# 1_MCU.net
KiCad netlist of a schematic drawn in Altium Designer
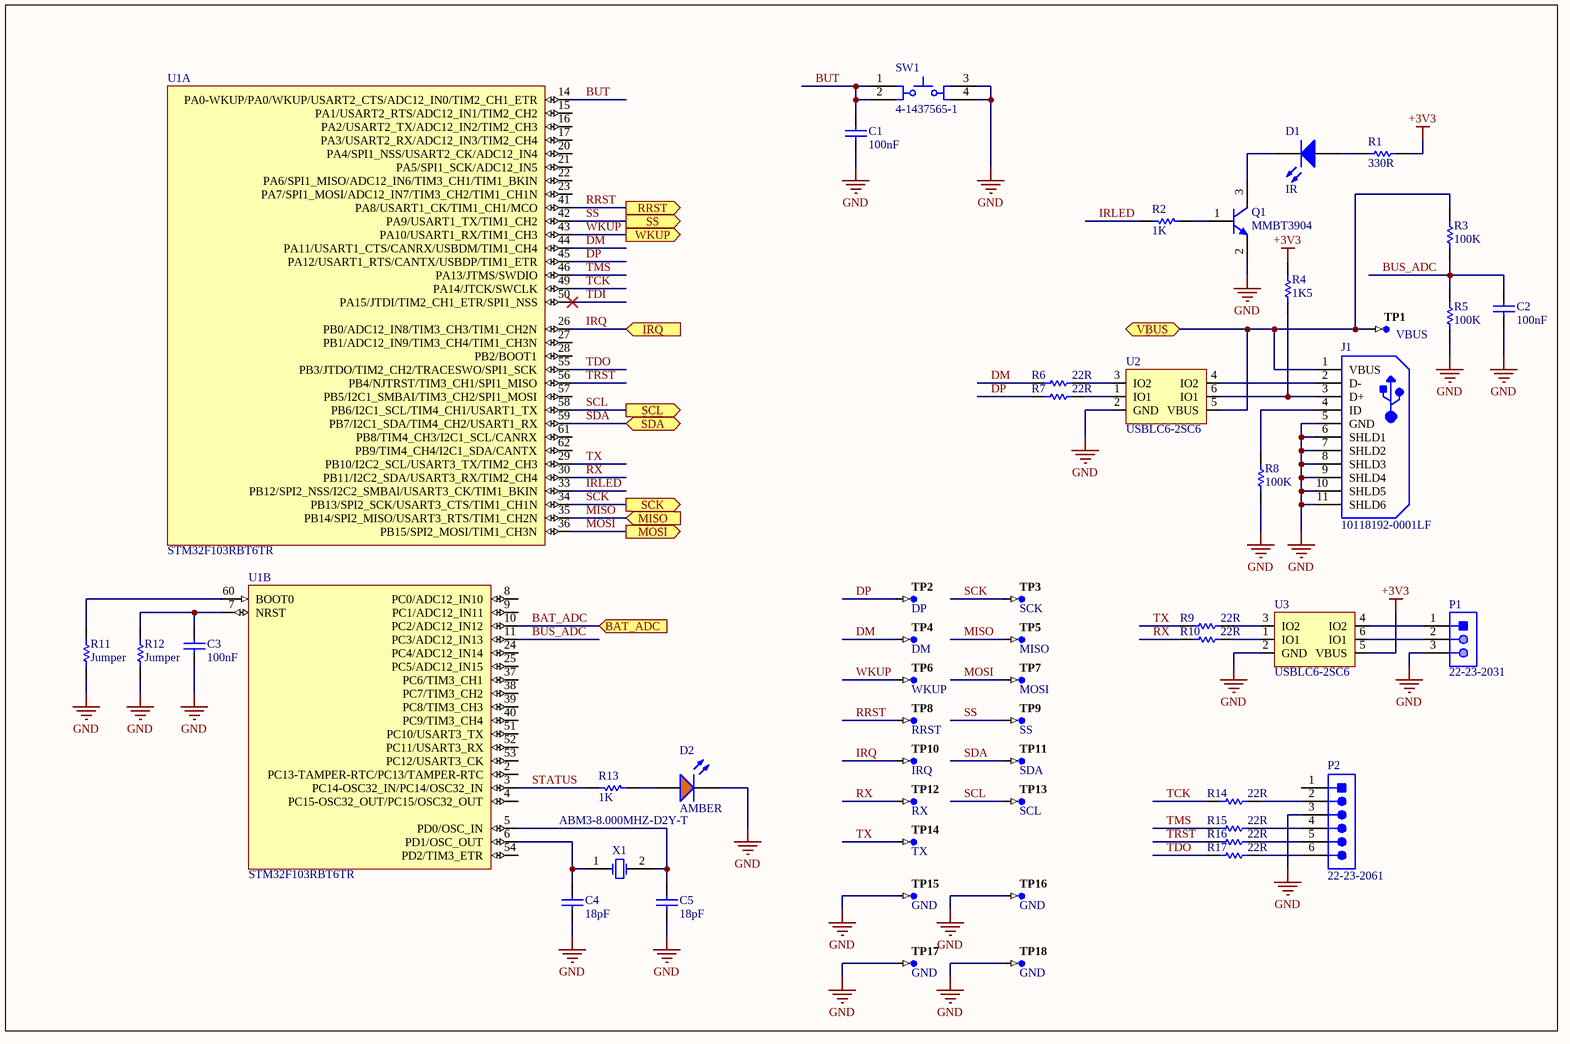
[diagram p0: 1_MCU.SchDoc]

(export (version "E")
  (design (tool "Eeschema 10.0.6"))
  (components
    (comp (ref "C1")
      (value "100nF")
      (footprint "CAPC0603(1608)100_M")
      (description "CAP 100nF 25V ±20% 0603 (1608 Metric) Thickness 1mm SMD")
      (fields (field (name "TOLERANCE") "Â±20%"))
      (libsource (lib "Altium Content Vault") (part "CAP"))
    )
    (comp (ref "C2")
      (value "100nF")
      (footprint "CAPC0603(1608)100_M")
      (description "CAP 100nF 25V ±20% 0603 (1608 Metric) Thickness 1mm SMD")
      (fields (field (name "TOLERANCE") "Â±20%"))
      (libsource (lib "Altium Content Vault") (part "CAP"))
    )
    (comp (ref "C3")
      (value "100nF")
      (footprint "CAPC0603(1608)100_M")
      (description "CAP 100nF 25V ±20% 0603 (1608 Metric) Thickness 1mm SMD")
      (fields (field (name "TOLERANCE") "Â±20%"))
      (libsource (lib "Altium Content Vault") (part "CAP"))
    )
    (comp (ref "C4")
      (value "18pF")
      (footprint "CAPC0603(1608)100_M")
      (description "CAP 18pF 25V ±0.5pF 0603 (1608 Metric) Thickness 1mm SMD")
      (fields (field (name "TOLERANCE") "Â±0.5pF"))
      (libsource (lib "Altium Content Vault") (part "CAP"))
    )
    (comp (ref "C5")
      (value "18pF")
      (footprint "CAPC0603(1608)100_M")
      (description "CAP 18pF 25V ±0.5pF 0603 (1608 Metric) Thickness 1mm SMD")
      (fields (field (name "TOLERANCE") "Â±0.5pF"))
      (libsource (lib "Altium Content Vault") (part "CAP"))
    )
    (comp (ref "D1")
      (value "IR")
      (footprint "Type 3mm")
      (description "THT LED round mono-color color lens, WL-TMRW, Super Red")
      (fields (field (name "PARTNUMBER") "151031SS04000") (field (name "MANUFACTURER") "Wuerth Elektronik"))
      (libsource (lib "Altium Content Vault") (part "WE-LED_K1A2-2"))
    )
    (comp (ref "D2")
      (value "AMBER")
      (footprint "LTST-C171AKT_V")
      (description "LED AMBER CLR THIN 0805 SMD")
      (fields (field (name "PARTNUMBER") "LTST-C171AKT") (field (name "MANUFACTURER") "Lite-On"))
      (libsource (lib "Altium Content Vault") (part "LED_AMBER_AC"))
    )
    (comp (ref "J1")
      (value "10118192-0001LF")
      (footprint "FCI-10118192-0001LF-5_V")
      (description "Micro USB B Type Receptacle, -55 to 85 degC, 5-Pin SMD, RoHS, Tape and Reel")
      (fields (field (name "MANUFACTURER") "FCI"))
      (libsource (lib "Altium Content Vault") (part "USB-5-6SHLD"))
    )
    (comp (ref "P1")
      (value "22-23-2031")
      (footprint "MOLX-22-23-2031_V")
      (description "Male Header, Pitch 2.54 mm, 1 x 3 Position, Height 8.18 mm, Tail Length 3.56 mm, RoHS, Bulk")
      (fields (field (name "MANUFACTURER") "Molex"))
      (libsource (lib "Altium Content Vault") (part "CN-1P-M-R3"))
    )
    (comp (ref "P2")
      (value "22-23-2061")
      (footprint "MOLX-22-23-2061_V")
      (fields (field (name "MANUFACTURER") "Molex"))
      (libsource (lib "Altium Content Vault") (part "CN-1P-M-R6"))
    )
    (comp (ref "Q1")
      (value "MMBT3904")
      (footprint "FAIR-SOT23-3_V")
      (description "NPN General Purpose Amplifier, 40 V, 0.2 A, -55 to 150 degC, 3-Pin SOT23, RoHS, Tape and Reel")
      (fields (field (name "TOLERANCE") "30ppm"))
      (libsource (lib "Altium Content Vault") (part "BJT-NPN-BEC-3"))
    )
    (comp (ref "R1")
      (value "330R")
      (footprint "RESC0603(1608)_M")
      (description "330R 0.1W 1% 0603 (1608 Metric)  SMD")
      (fields (field (name "TOLERANCE") "1 %") (field (name "POWER") "0.1 W"))
      (libsource (lib "Altium Content Vault") (part "RES"))
    )
    (comp (ref "R2")
      (value "1K")
      (footprint "RESC0603(1608)_M")
      (description "1K 0.1W 1% 0603 (1608 Metric)  SMD")
      (fields (field (name "TOLERANCE") "1 %") (field (name "POWER") "0.1 W"))
      (libsource (lib "Altium Content Vault") (part "RES"))
    )
    (comp (ref "R3")
      (value "100K")
      (footprint "RESC0603(1608)_M")
      (description "100K 0.1W 1% 0603 (1608 Metric)  SMD")
      (fields (field (name "POWER") "0.1 W") (field (name "TOLERANCE") "1 %"))
      (libsource (lib "Altium Content Vault") (part "RES"))
    )
    (comp (ref "R4")
      (value "1K5")
      (footprint "RESC0603(1608)_M")
      (description "1K5 0.1W 1% 0603 (1608 Metric)  SMD")
      (fields (field (name "POWER") "0.1 W") (field (name "TOLERANCE") "1 %"))
      (libsource (lib "Altium Content Vault") (part "RES"))
    )
    (comp (ref "R5")
      (value "100K")
      (footprint "RESC0603(1608)_M")
      (description "100K 0.1W 1% 0603 (1608 Metric)  SMD")
      (fields (field (name "POWER") "0.1 W") (field (name "TOLERANCE") "1 %"))
      (libsource (lib "Altium Content Vault") (part "RES"))
    )
    (comp (ref "R6")
      (value "22R")
      (footprint "RESC0603(1608)_M")
      (description "22R 0.1W 1% 0603 (1608 Metric)  SMD")
      (fields (field (name "POWER") "0.1 W") (field (name "TOLERANCE") "1 %"))
      (libsource (lib "Altium Content Vault") (part "RES"))
    )
    (comp (ref "R7")
      (value "22R")
      (footprint "RESC0603(1608)_M")
      (description "22R 0.1W 1% 0603 (1608 Metric)  SMD")
      (fields (field (name "POWER") "0.1 W") (field (name "TOLERANCE") "1 %"))
      (libsource (lib "Altium Content Vault") (part "RES"))
    )
    (comp (ref "R8")
      (value "100K")
      (footprint "RESC0603(1608)_M")
      (description "100K 0.1W 1% 0603 (1608 Metric)  SMD")
      (fields (field (name "POWER") "0.1 W") (field (name "TOLERANCE") "1 %"))
      (libsource (lib "Altium Content Vault") (part "RES"))
    )
    (comp (ref "R9")
      (value "22R")
      (footprint "RESC0603(1608)_M")
      (description "22R 0.1W 1% 0603 (1608 Metric)  SMD")
      (fields (field (name "POWER") "0.1 W") (field (name "TOLERANCE") "1 %"))
      (libsource (lib "Altium Content Vault") (part "RES"))
    )
    (comp (ref "R10")
      (value "22R")
      (footprint "RESC0603(1608)_M")
      (description "22R 0.1W 1% 0603 (1608 Metric)  SMD")
      (fields (field (name "POWER") "0.1 W") (field (name "TOLERANCE") "1 %"))
      (libsource (lib "Altium Content Vault") (part "RES"))
    )
    (comp (ref "R11")
      (value "Jumper")
      (footprint "RESC0805(2012)_M")
      (description "Jumper 0805 (2012 Metric)")
      (fields (field (name "TOLERANCE") "None"))
      (libsource (lib "Altium Content Vault") (part "RES"))
    )
    (comp (ref "R12")
      (value "Jumper")
      (footprint "RESC0805(2012)_M")
      (description "Jumper 0805 (2012 Metric)")
      (fields (field (name "TOLERANCE") "None"))
      (libsource (lib "Altium Content Vault") (part "RES"))
    )
    (comp (ref "R13")
      (value "1K")
      (footprint "RESC0603(1608)_M")
      (description "1K 0.1W 1% 0603 (1608 Metric)  SMD")
      (fields (field (name "TOLERANCE") "1 %") (field (name "POWER") "0.1 W"))
      (libsource (lib "Altium Content Vault") (part "RES"))
    )
    (comp (ref "R14")
      (value "22R")
      (footprint "RESC0603(1608)_M")
      (description "22R 0.1W 1% 0603 (1608 Metric)  SMD")
      (fields (field (name "POWER") "0.1 W") (field (name "TOLERANCE") "1 %"))
      (libsource (lib "Altium Content Vault") (part "RES"))
    )
    (comp (ref "R15")
      (value "22R")
      (footprint "RESC0603(1608)_M")
      (description "22R 0.1W 1% 0603 (1608 Metric)  SMD")
      (fields (field (name "POWER") "0.1 W") (field (name "TOLERANCE") "1 %"))
      (libsource (lib "Altium Content Vault") (part "RES"))
    )
    (comp (ref "R16")
      (value "22R")
      (footprint "RESC0603(1608)_M")
      (description "22R 0.1W 1% 0603 (1608 Metric)  SMD")
      (fields (field (name "POWER") "0.1 W") (field (name "TOLERANCE") "1 %"))
      (libsource (lib "Altium Content Vault") (part "RES"))
    )
    (comp (ref "R17")
      (value "22R")
      (footprint "RESC0603(1608)_M")
      (description "22R 0.1W 1% 0603 (1608 Metric)  SMD")
      (fields (field (name "POWER") "0.1 W") (field (name "TOLERANCE") "1 %"))
      (libsource (lib "Altium Content Vault") (part "RES"))
    )
    (comp (ref "SW1")
      (value "4-1437565-1")
      (footprint "TECO-4-1437565-1_V")
      (description "Tactile Switch, 50 mA, 12 VDC, -20 to 85 degC, 4-Pin SMD, RoHS, Bulk")
      (fields (field (name "MANUFACTURER") "TEConnectivity/AMPBrand"))
      (libsource (lib "Altium Content Vault") (part "SW-SPST-NO-4"))
    )
    (comp (ref "TP1")
      (value "VBUS")
      (footprint "TP-SM-C-100")
      (description "Test Point, Surface Mount, Circular, Pad Diameter 1 mm")
      (fields (field (name "PARTNUMBER") "TP-SM-C-100") (field (name "MANUFACTURER") "No Vendor"))
      (libsource (lib "Altium Content Vault") (part "TP-SM"))
    )
    (comp (ref "TP2")
      (value "DP")
      (footprint "TP-SM-C-100")
      (description "Test Point, Surface Mount, Circular, Pad Diameter 1 mm")
      (fields (field (name "PARTNUMBER") "TP-SM-C-100") (field (name "MANUFACTURER") "No Vendor"))
      (libsource (lib "Altium Content Vault") (part "TP-SM"))
    )
    (comp (ref "TP3")
      (value "SCK")
      (footprint "TP-SM-C-100")
      (description "Test Point, Surface Mount, Circular, Pad Diameter 1 mm")
      (fields (field (name "PARTNUMBER") "TP-SM-C-100") (field (name "MANUFACTURER") "No Vendor"))
      (libsource (lib "Altium Content Vault") (part "TP-SM"))
    )
    (comp (ref "TP4")
      (value "DM")
      (footprint "TP-SM-C-100")
      (description "Test Point, Surface Mount, Circular, Pad Diameter 1 mm")
      (fields (field (name "PARTNUMBER") "TP-SM-C-100") (field (name "MANUFACTURER") "No Vendor"))
      (libsource (lib "Altium Content Vault") (part "TP-SM"))
    )
    (comp (ref "TP5")
      (value "MISO")
      (footprint "TP-SM-C-100")
      (description "Test Point, Surface Mount, Circular, Pad Diameter 1 mm")
      (fields (field (name "PARTNUMBER") "TP-SM-C-100") (field (name "MANUFACTURER") "No Vendor"))
      (libsource (lib "Altium Content Vault") (part "TP-SM"))
    )
    (comp (ref "TP6")
      (value "WKUP")
      (footprint "TP-SM-C-100")
      (description "Test Point, Surface Mount, Circular, Pad Diameter 1 mm")
      (fields (field (name "PARTNUMBER") "TP-SM-C-100") (field (name "MANUFACTURER") "No Vendor"))
      (libsource (lib "Altium Content Vault") (part "TP-SM"))
    )
    (comp (ref "TP7")
      (value "MOSI")
      (footprint "TP-SM-C-100")
      (description "Test Point, Surface Mount, Circular, Pad Diameter 1 mm")
      (fields (field (name "PARTNUMBER") "TP-SM-C-100") (field (name "MANUFACTURER") "No Vendor"))
      (libsource (lib "Altium Content Vault") (part "TP-SM"))
    )
    (comp (ref "TP8")
      (value "RRST")
      (footprint "TP-SM-C-100")
      (description "Test Point, Surface Mount, Circular, Pad Diameter 1 mm")
      (fields (field (name "PARTNUMBER") "TP-SM-C-100") (field (name "MANUFACTURER") "No Vendor"))
      (libsource (lib "Altium Content Vault") (part "TP-SM"))
    )
    (comp (ref "TP9")
      (value "SS")
      (footprint "TP-SM-C-100")
      (description "Test Point, Surface Mount, Circular, Pad Diameter 1 mm")
      (fields (field (name "PARTNUMBER") "TP-SM-C-100") (field (name "MANUFACTURER") "No Vendor"))
      (libsource (lib "Altium Content Vault") (part "TP-SM"))
    )
    (comp (ref "TP10")
      (value "IRQ")
      (footprint "TP-SM-C-100")
      (description "Test Point, Surface Mount, Circular, Pad Diameter 1 mm")
      (fields (field (name "PARTNUMBER") "TP-SM-C-100") (field (name "MANUFACTURER") "No Vendor"))
      (libsource (lib "Altium Content Vault") (part "TP-SM"))
    )
    (comp (ref "TP11")
      (value "SDA")
      (footprint "TP-SM-C-100")
      (description "Test Point, Surface Mount, Circular, Pad Diameter 1 mm")
      (fields (field (name "PARTNUMBER") "TP-SM-C-100") (field (name "MANUFACTURER") "No Vendor"))
      (libsource (lib "Altium Content Vault") (part "TP-SM"))
    )
    (comp (ref "TP12")
      (value "RX")
      (footprint "TP-SM-C-100")
      (description "Test Point, Surface Mount, Circular, Pad Diameter 1 mm")
      (fields (field (name "PARTNUMBER") "TP-SM-C-100") (field (name "MANUFACTURER") "No Vendor"))
      (libsource (lib "Altium Content Vault") (part "TP-SM"))
    )
    (comp (ref "TP13")
      (value "SCL")
      (footprint "TP-SM-C-100")
      (description "Test Point, Surface Mount, Circular, Pad Diameter 1 mm")
      (fields (field (name "PARTNUMBER") "TP-SM-C-100") (field (name "MANUFACTURER") "No Vendor"))
      (libsource (lib "Altium Content Vault") (part "TP-SM"))
    )
    (comp (ref "TP14")
      (value "TX")
      (footprint "TP-SM-C-100")
      (description "Test Point, Surface Mount, Circular, Pad Diameter 1 mm")
      (fields (field (name "PARTNUMBER") "TP-SM-C-100") (field (name "MANUFACTURER") "No Vendor"))
      (libsource (lib "Altium Content Vault") (part "TP-SM"))
    )
    (comp (ref "TP15")
      (value "GND")
      (footprint "TP-SM-C-100")
      (description "Test Point, Surface Mount, Circular, Pad Diameter 1 mm")
      (fields (field (name "PARTNUMBER") "TP-SM-C-100") (field (name "MANUFACTURER") "No Vendor"))
      (libsource (lib "Altium Content Vault") (part "TP-SM"))
    )
    (comp (ref "TP16")
      (value "GND")
      (footprint "TP-SM-C-100")
      (description "Test Point, Surface Mount, Circular, Pad Diameter 1 mm")
      (fields (field (name "PARTNUMBER") "TP-SM-C-100") (field (name "MANUFACTURER") "No Vendor"))
      (libsource (lib "Altium Content Vault") (part "TP-SM"))
    )
    (comp (ref "TP17")
      (value "GND")
      (footprint "TP-SM-C-100")
      (description "Test Point, Surface Mount, Circular, Pad Diameter 1 mm")
      (fields (field (name "PARTNUMBER") "TP-SM-C-100") (field (name "MANUFACTURER") "No Vendor"))
      (libsource (lib "Altium Content Vault") (part "TP-SM"))
    )
    (comp (ref "TP18")
      (value "GND")
      (footprint "TP-SM-C-100")
      (description "Test Point, Surface Mount, Circular, Pad Diameter 1 mm")
      (fields (field (name "PARTNUMBER") "TP-SM-C-100") (field (name "MANUFACTURER") "No Vendor"))
      (libsource (lib "Altium Content Vault") (part "TP-SM"))
    )
    (comp (ref "U1")
      (value "STM32F103RBT6TR")
      (footprint "STM-LQFP64_N")
      (libsource (lib "Altium Content Vault") (part "MC-ARM-STM32F103X8_B-SQ64"))
    )
    (comp (ref "U2")
      (value "USBLC6-2SC6")
      (footprint "SOT95P280X145-6N")
      (description "TVS DIODE 5.25V 17V SOT23-6")
      (fields (field (name "MANUFACTURER") "STMicroelectronics"))
      (libsource (lib "PositionMiniModule") (part "USBLC6-2SC6"))
    )
    (comp (ref "U3")
      (value "USBLC6-2SC6")
      (footprint "SOT95P280X145-6N")
      (description "TVS DIODE 5.25V 17V SOT23-6")
      (fields (field (name "MANUFACTURER") "STMicroelectronics"))
      (libsource (lib "PositionMiniModule") (part "USBLC6-2SC6"))
    )
    (comp (ref "X1")
      (value "ABM3-8.000MHZ-D2Y-T")
      (footprint "ABRA-ABM3-2_V")
      (description "Miniature Ceramic Crystal, 8 MHz, -40 to 85 degC, 2-Pin SMD, RoHS, Tape and Reel")
      (fields (field (name "MANUFACTURER") "ABRACON") (field (name "TOLERANCE") "20PPM"))
      (libsource (lib "Altium Content Vault") (part "XTAL_1-2-2"))
    )
  )
  (nets
    (net (code "1") (name "+3V3") (class "Default")
      (node (ref "R1") (pin "2") (pinfunction "2_2") (pintype "passive"))
      (node (ref "R4") (pin "2") (pinfunction "2_2") (pintype "passive"))
      (node (ref "U3") (pin "5") (pinfunction "VBUS_5") (pintype "passive"))
    )
    (net (code "2") (name "/BAT_ADC") (class "Default")
      (node (ref "U1") (pin "10") (pinfunction "PC2/ADC12_IN12_10") (pintype "bidirectional"))
    )
    (net (code "3") (name "/BUS_ADC") (class "Default")
      (node (ref "C2") (pin "1") (pinfunction "1_1") (pintype "passive"))
      (node (ref "R3") (pin "1") (pinfunction "1_1") (pintype "passive"))
      (node (ref "R5") (pin "2") (pinfunction "2_2") (pintype "passive"))
      (node (ref "U1") (pin "11") (pinfunction "PC3/ADC12_IN13_11") (pintype "bidirectional"))
    )
    (net (code "4") (name "/BUT") (class "Default")
      (node (ref "C1") (pin "1") (pinfunction "1_1") (pintype "passive"))
      (node (ref "SW1") (pin "1") (pinfunction "1_1") (pintype "passive"))
      (node (ref "SW1") (pin "2") (pinfunction "2_2") (pintype "passive"))
      (node (ref "U1") (pin "14") (pinfunction "PA0-WKUP/PA0/WKUP/USART2_CTS/ADC12_IN0/TIM2_CH1_ETR_14") (pintype "bidirectional"))
    )
    (net (code "5") (name "/DM") (class "Default")
      (node (ref "R6") (pin "1") (pinfunction "1_1") (pintype "passive"))
      (node (ref "TP4") (pin "1") (pinfunction "1_1") (pintype "input"))
      (node (ref "U1") (pin "44") (pinfunction "PA11/USART1_CTS/CANRX/USBDM/TIM1_CH4_44") (pintype "bidirectional"))
    )
    (net (code "6") (name "/DP") (class "Default")
      (node (ref "R7") (pin "1") (pinfunction "1_1") (pintype "passive"))
      (node (ref "TP2") (pin "1") (pinfunction "1_1") (pintype "input"))
      (node (ref "U1") (pin "45") (pinfunction "PA12/USART1_RTS/CANTX/USBDP/TIM1_ETR_45") (pintype "bidirectional"))
    )
    (net (code "7") (name "/IRLED") (class "Default")
      (node (ref "R2") (pin "2") (pinfunction "2_2") (pintype "passive"))
      (node (ref "U1") (pin "33") (pinfunction "PB12/SPI2_NSS/I2C2_SMBAl/USART3_CK/TIM1_BKIN_33") (pintype "bidirectional"))
    )
    (net (code "8") (name "/IRQ") (class "Default")
      (node (ref "TP10") (pin "1") (pinfunction "1_1") (pintype "input"))
      (node (ref "U1") (pin "26") (pinfunction "PB0/ADC12_IN8/TIM3_CH3/TIM1_CH2N_26") (pintype "bidirectional"))
    )
    (net (code "9") (name "/MISO") (class "Default")
      (node (ref "TP5") (pin "1") (pinfunction "1_1") (pintype "input"))
      (node (ref "U1") (pin "35") (pinfunction "PB14/SPI2_MISO/USART3_RTS/TIM1_CH2N_35") (pintype "bidirectional"))
    )
    (net (code "10") (name "/MOSI") (class "Default")
      (node (ref "TP7") (pin "1") (pinfunction "1_1") (pintype "input"))
      (node (ref "U1") (pin "36") (pinfunction "PB15/SPI2_MOSI/TIM1_CH3N_36") (pintype "bidirectional"))
    )
    (net (code "11") (name "/RRST") (class "Default")
      (node (ref "TP8") (pin "1") (pinfunction "1_1") (pintype "input"))
      (node (ref "U1") (pin "41") (pinfunction "PA8/USART1_CK/TIM1_CH1/MCO_41") (pintype "bidirectional"))
    )
    (net (code "12") (name "/RX") (class "Default")
      (node (ref "R10") (pin "1") (pinfunction "1_1") (pintype "passive"))
      (node (ref "TP12") (pin "1") (pinfunction "1_1") (pintype "input"))
      (node (ref "U1") (pin "30") (pinfunction "PB11/I2C2_SDA/USART3_RX/TIM2_CH4_30") (pintype "bidirectional"))
    )
    (net (code "13") (name "/SCK") (class "Default")
      (node (ref "TP3") (pin "1") (pinfunction "1_1") (pintype "input"))
      (node (ref "U1") (pin "34") (pinfunction "PB13/SPI2_SCK/USART3_CTS/TIM1_CH1N_34") (pintype "bidirectional"))
    )
    (net (code "14") (name "/SCL") (class "Default")
      (node (ref "TP13") (pin "1") (pinfunction "1_1") (pintype "input"))
      (node (ref "U1") (pin "58") (pinfunction "PB6/I2C1_SCL/TIM4_CH1/USART1_TX_58") (pintype "bidirectional"))
    )
    (net (code "15") (name "/SDA") (class "Default")
      (node (ref "TP11") (pin "1") (pinfunction "1_1") (pintype "input"))
      (node (ref "U1") (pin "59") (pinfunction "PB7/I2C1_SDA/TIM4_CH2/USART1_RX_59") (pintype "bidirectional"))
    )
    (net (code "16") (name "/SS") (class "Default")
      (node (ref "TP9") (pin "1") (pinfunction "1_1") (pintype "input"))
      (node (ref "U1") (pin "42") (pinfunction "PA9/USART1_TX/TIM1_CH2_42") (pintype "bidirectional"))
    )
    (net (code "17") (name "/STATUS") (class "Default")
      (node (ref "R13") (pin "2") (pinfunction "2_2") (pintype "passive"))
      (node (ref "U1") (pin "3") (pinfunction "PC14-OSC32_IN/PC14/OSC32_IN_3") (pintype "bidirectional"))
    )
    (net (code "18") (name "/TCK") (class "Default")
      (node (ref "R14") (pin "1") (pinfunction "1_1") (pintype "passive"))
      (node (ref "U1") (pin "49") (pinfunction "PA14/JTCK/SWCLK_49") (pintype "bidirectional"))
    )
    (net (code "19") (name "/TDI") (class "Default")
      (node (ref "U1") (pin "50") (pinfunction "PA15/JTDI/TIM2_CH1_ETR/SPI1_NSS_50") (pintype "bidirectional+no_connect"))
    )
    (net (code "20") (name "/TDO") (class "Default")
      (node (ref "R17") (pin "1") (pinfunction "1_1") (pintype "passive"))
      (node (ref "U1") (pin "55") (pinfunction "PB3/JTDO/TIM2_CH2/TRACESWO/SPI1_SCK_55") (pintype "bidirectional"))
    )
    (net (code "21") (name "/TMS") (class "Default")
      (node (ref "R15") (pin "1") (pinfunction "1_1") (pintype "passive"))
      (node (ref "U1") (pin "46") (pinfunction "PA13/JTMS/SWDIO_46") (pintype "bidirectional"))
    )
    (net (code "22") (name "/TRST") (class "Default")
      (node (ref "R16") (pin "1") (pinfunction "1_1") (pintype "passive"))
      (node (ref "U1") (pin "56") (pinfunction "PB4/NJTRST/TIM3_CH1/SPI1_MISO_56") (pintype "bidirectional"))
    )
    (net (code "23") (name "/TX") (class "Default")
      (node (ref "R9") (pin "1") (pinfunction "1_1") (pintype "passive"))
      (node (ref "TP14") (pin "1") (pinfunction "1_1") (pintype "input"))
      (node (ref "U1") (pin "29") (pinfunction "PB10/I2C2_SCL/USART3_TX/TIM2_CH3_29") (pintype "bidirectional"))
    )
    (net (code "24") (name "/VBUS") (class "Default")
      (node (ref "J1") (pin "1") (pinfunction "VBUS_1") (pintype "passive"))
      (node (ref "R3") (pin "2") (pinfunction "2_2") (pintype "passive"))
      (node (ref "TP1") (pin "1") (pinfunction "1_1") (pintype "input"))
      (node (ref "U2") (pin "5") (pinfunction "VBUS_5") (pintype "passive"))
    )
    (net (code "25") (name "/WKUP") (class "Default")
      (node (ref "TP6") (pin "1") (pinfunction "1_1") (pintype "input"))
      (node (ref "U1") (pin "43") (pinfunction "PA10/USART1_RX/TIM1_CH3_43") (pintype "bidirectional"))
    )
    (net (code "26") (name "GND") (class "Default")
      (node (ref "C1") (pin "2") (pinfunction "2_2") (pintype "passive"))
      (node (ref "C2") (pin "2") (pinfunction "2_2") (pintype "passive"))
      (node (ref "C3") (pin "2") (pinfunction "2_2") (pintype "passive"))
      (node (ref "C4") (pin "1") (pinfunction "1_1") (pintype "passive"))
      (node (ref "C5") (pin "1") (pinfunction "1_1") (pintype "passive"))
      (node (ref "D2") (pin "C") (pinfunction "C_C") (pintype "passive"))
      (node (ref "J1") (pin "10") (pinfunction "SHLD5_10") (pintype "passive"))
      (node (ref "J1") (pin "11") (pinfunction "SHLD6_11") (pintype "passive"))
      (node (ref "J1") (pin "5") (pinfunction "GND_5") (pintype "passive"))
      (node (ref "J1") (pin "6") (pinfunction "SHLD1_6") (pintype "passive"))
      (node (ref "J1") (pin "7") (pinfunction "SHLD2_7") (pintype "passive"))
      (node (ref "J1") (pin "8") (pinfunction "SHLD3_8") (pintype "passive"))
      (node (ref "J1") (pin "9") (pinfunction "SHLD4_9") (pintype "passive"))
      (node (ref "P1") (pin "3") (pinfunction "3_3") (pintype "passive"))
      (node (ref "P2") (pin "3") (pinfunction "3_3") (pintype "passive"))
      (node (ref "Q1") (pin "2") (pinfunction "E_2") (pintype "passive"))
      (node (ref "R11") (pin "1") (pinfunction "1_1") (pintype "passive"))
      (node (ref "R12") (pin "1") (pinfunction "1_1") (pintype "passive"))
      (node (ref "R5") (pin "1") (pinfunction "1_1") (pintype "passive"))
      (node (ref "R8") (pin "1") (pinfunction "1_1") (pintype "passive"))
      (node (ref "SW1") (pin "3") (pinfunction "3_3") (pintype "passive"))
      (node (ref "SW1") (pin "4") (pinfunction "4_4") (pintype "passive"))
      (node (ref "TP15") (pin "1") (pinfunction "1_1") (pintype "input"))
      (node (ref "TP16") (pin "1") (pinfunction "1_1") (pintype "input"))
      (node (ref "TP17") (pin "1") (pinfunction "1_1") (pintype "input"))
      (node (ref "TP18") (pin "1") (pinfunction "1_1") (pintype "input"))
      (node (ref "U2") (pin "2") (pinfunction "GND_2") (pintype "passive"))
      (node (ref "U3") (pin "2") (pinfunction "GND_2") (pintype "passive"))
    )
    (net (code "27") (name "Net-(D1-A)") (class "Default")
      (node (ref "D1") (pin "2") (pinfunction "A_2") (pintype "passive"))
      (node (ref "R1") (pin "1") (pinfunction "1_1") (pintype "passive"))
    )
    (net (code "28") (name "Net-(D1-K)") (class "Default")
      (node (ref "D1") (pin "1") (pinfunction "K_1") (pintype "passive"))
      (node (ref "Q1") (pin "3") (pinfunction "C_3") (pintype "passive"))
    )
    (net (code "29") (name "Net-(D2-PadA)") (class "Default")
      (node (ref "D2") (pin "A") (pinfunction "A_A") (pintype "passive"))
      (node (ref "R13") (pin "1") (pinfunction "1_1") (pintype "passive"))
    )
    (net (code "30") (name "Net-(J1-D+)") (class "Default")
      (node (ref "J1") (pin "3") (pinfunction "D+_3") (pintype "passive"))
      (node (ref "R4") (pin "1") (pinfunction "1_1") (pintype "passive"))
      (node (ref "U2") (pin "6") (pinfunction "IO1_6") (pintype "passive"))
    )
    (net (code "31") (name "Net-(J1-D-)") (class "Default")
      (node (ref "J1") (pin "2") (pinfunction "D-_2") (pintype "passive"))
      (node (ref "U2") (pin "4") (pinfunction "IO2_4") (pintype "passive"))
    )
    (net (code "32") (name "Net-(J1-ID)") (class "Default")
      (node (ref "J1") (pin "4") (pinfunction "ID_4") (pintype "passive"))
      (node (ref "R8") (pin "2") (pinfunction "2_2") (pintype "passive"))
    )
    (net (code "33") (name "Net-(P1-Pad1)") (class "Default")
      (node (ref "P1") (pin "1") (pinfunction "1_1") (pintype "passive"))
      (node (ref "U3") (pin "4") (pinfunction "IO2_4") (pintype "passive"))
    )
    (net (code "34") (name "Net-(P1-Pad2)") (class "Default")
      (node (ref "P1") (pin "2") (pinfunction "2_2") (pintype "passive"))
      (node (ref "U3") (pin "6") (pinfunction "IO1_6") (pintype "passive"))
    )
    (net (code "35") (name "Net-(P2-Pad2)") (class "Default")
      (node (ref "P2") (pin "2") (pinfunction "2_2") (pintype "passive"))
      (node (ref "R14") (pin "2") (pinfunction "2_2") (pintype "passive"))
    )
    (net (code "36") (name "Net-(P2-Pad4)") (class "Default")
      (node (ref "P2") (pin "4") (pinfunction "4_4") (pintype "passive"))
      (node (ref "R15") (pin "2") (pinfunction "2_2") (pintype "passive"))
    )
    (net (code "37") (name "Net-(P2-Pad5)") (class "Default")
      (node (ref "P2") (pin "5") (pinfunction "5_5") (pintype "passive"))
      (node (ref "R16") (pin "2") (pinfunction "2_2") (pintype "passive"))
    )
    (net (code "38") (name "Net-(P2-Pad6)") (class "Default")
      (node (ref "P2") (pin "6") (pinfunction "6_6") (pintype "passive"))
      (node (ref "R17") (pin "2") (pinfunction "2_2") (pintype "passive"))
    )
    (net (code "39") (name "Net-(Q1-B)") (class "Default")
      (node (ref "Q1") (pin "1") (pinfunction "B_1") (pintype "passive"))
      (node (ref "R2") (pin "1") (pinfunction "1_1") (pintype "passive"))
    )
    (net (code "40") (name "Net-(R6-Pad2)") (class "Default")
      (node (ref "R6") (pin "2") (pinfunction "2_2") (pintype "passive"))
      (node (ref "U2") (pin "3") (pinfunction "IO2_3") (pintype "passive"))
    )
    (net (code "41") (name "Net-(R7-Pad2)") (class "Default")
      (node (ref "R7") (pin "2") (pinfunction "2_2") (pintype "passive"))
      (node (ref "U2") (pin "1") (pinfunction "IO1_1") (pintype "passive"))
    )
    (net (code "42") (name "Net-(R9-Pad2)") (class "Default")
      (node (ref "R9") (pin "2") (pinfunction "2_2") (pintype "passive"))
      (node (ref "U3") (pin "3") (pinfunction "IO2_3") (pintype "passive"))
    )
    (net (code "43") (name "Net-(R10-Pad2)") (class "Default")
      (node (ref "R10") (pin "2") (pinfunction "2_2") (pintype "passive"))
      (node (ref "U3") (pin "1") (pinfunction "IO1_1") (pintype "passive"))
    )
    (net (code "44") (name "Net-(U1B-BOOT0)") (class "Default")
      (node (ref "R11") (pin "2") (pinfunction "2_2") (pintype "passive"))
      (node (ref "U1") (pin "60") (pinfunction "BOOT0_60") (pintype "input"))
    )
    (net (code "45") (name "Net-(U1B-NRST)") (class "Default")
      (node (ref "C3") (pin "1") (pinfunction "1_1") (pintype "passive"))
      (node (ref "R12") (pin "2") (pinfunction "2_2") (pintype "passive"))
      (node (ref "U1") (pin "7") (pinfunction "NRST_7") (pintype "bidirectional"))
    )
    (net (code "46") (name "Net-(U1B-PD0{slash}OSC_IN)") (class "Default")
      (node (ref "C5") (pin "2") (pinfunction "2_2") (pintype "passive"))
      (node (ref "U1") (pin "5") (pinfunction "PD0/OSC_IN_5") (pintype "bidirectional"))
      (node (ref "X1") (pin "2") (pinfunction "X2_2") (pintype "passive"))
    )
    (net (code "47") (name "Net-(U1B-PD1{slash}OSC_OUT)") (class "Default")
      (node (ref "C4") (pin "2") (pinfunction "2_2") (pintype "passive"))
      (node (ref "U1") (pin "6") (pinfunction "PD1/OSC_OUT_6") (pintype "bidirectional"))
      (node (ref "X1") (pin "1") (pinfunction "X1_1") (pintype "passive"))
    )
    (net (code "48") (name "unconnected-(P2-Pad1)") (class "Default")
      (node (ref "P2") (pin "1") (pinfunction "1_1") (pintype "passive"))
    )
    (net (code "49") (name "unconnected-(U1A-PA1{slash}USART2_RTS{slash}ADC12_IN1{slash}TIM2_CH2-Pad15)") (class "Default")
      (node (ref "U1") (pin "15") (pinfunction "PA1/USART2_RTS/ADC12_IN1/TIM2_CH2_15") (pintype "bidirectional"))
    )
    (net (code "50") (name "unconnected-(U1A-PA2{slash}USART2_TX{slash}ADC12_IN2{slash}TIM2_CH3-Pad16)") (class "Default")
      (node (ref "U1") (pin "16") (pinfunction "PA2/USART2_TX/ADC12_IN2/TIM2_CH3_16") (pintype "bidirectional"))
    )
    (net (code "51") (name "unconnected-(U1A-PA3{slash}USART2_RX{slash}ADC12_IN3{slash}TIM2_CH4-Pad17)") (class "Default")
      (node (ref "U1") (pin "17") (pinfunction "PA3/USART2_RX/ADC12_IN3/TIM2_CH4_17") (pintype "bidirectional"))
    )
    (net (code "52") (name "unconnected-(U1A-PA4{slash}SPI1_NSS{slash}USART2_CK{slash}ADC12_IN4-Pad20)") (class "Default")
      (node (ref "U1") (pin "20") (pinfunction "PA4/SPI1_NSS/USART2_CK/ADC12_IN4_20") (pintype "bidirectional"))
    )
    (net (code "53") (name "unconnected-(U1A-PA5{slash}SPI1_SCK{slash}ADC12_IN5-Pad21)") (class "Default")
      (node (ref "U1") (pin "21") (pinfunction "PA5/SPI1_SCK/ADC12_IN5_21") (pintype "bidirectional"))
    )
    (net (code "54") (name "unconnected-(U1A-PA6{slash}SPI1_MISO{slash}ADC12_IN6{slash}TIM3_CH1{slash}TIM1_BKIN-Pad22)") (class "Default")
      (node (ref "U1") (pin "22") (pinfunction "PA6/SPI1_MISO/ADC12_IN6/TIM3_CH1/TIM1_BKIN_22") (pintype "bidirectional"))
    )
    (net (code "55") (name "unconnected-(U1A-PA7{slash}SPI1_MOSI{slash}ADC12_IN7{slash}TIM3_CH2{slash}TIM1_CH1N-Pad23)") (class "Default")
      (node (ref "U1") (pin "23") (pinfunction "PA7/SPI1_MOSI/ADC12_IN7/TIM3_CH2/TIM1_CH1N_23") (pintype "bidirectional"))
    )
    (net (code "56") (name "unconnected-(U1A-PB1{slash}ADC12_IN9{slash}TIM3_CH4{slash}TIM1_CH3N-Pad27)") (class "Default")
      (node (ref "U1") (pin "27") (pinfunction "PB1/ADC12_IN9/TIM3_CH4/TIM1_CH3N_27") (pintype "bidirectional"))
    )
    (net (code "57") (name "unconnected-(U1A-PB2{slash}BOOT1-Pad28)") (class "Default")
      (node (ref "U1") (pin "28") (pinfunction "PB2/BOOT1_28") (pintype "bidirectional"))
    )
    (net (code "58") (name "unconnected-(U1A-PB5{slash}I2C1_SMBAI{slash}TIM3_CH2{slash}SPI1_MOSI-Pad57)") (class "Default")
      (node (ref "U1") (pin "57") (pinfunction "PB5/I2C1_SMBAI/TIM3_CH2/SPI1_MOSI_57") (pintype "bidirectional"))
    )
    (net (code "59") (name "unconnected-(U1A-PB8{slash}TIM4_CH3{slash}I2C1_SCL{slash}CANRX-Pad61)") (class "Default")
      (node (ref "U1") (pin "61") (pinfunction "PB8/TIM4_CH3/I2C1_SCL/CANRX_61") (pintype "bidirectional"))
    )
    (net (code "60") (name "unconnected-(U1A-PB9{slash}TIM4_CH4{slash}I2C1_SDA{slash}CANTX-Pad62)") (class "Default")
      (node (ref "U1") (pin "62") (pinfunction "PB9/TIM4_CH4/I2C1_SDA/CANTX_62") (pintype "bidirectional"))
    )
    (net (code "61") (name "unconnected-(U1B-PC0{slash}ADC12_IN10-Pad8)") (class "Default")
      (node (ref "U1") (pin "8") (pinfunction "PC0/ADC12_IN10_8") (pintype "bidirectional"))
    )
    (net (code "62") (name "unconnected-(U1B-PC1{slash}ADC12_IN11-Pad9)") (class "Default")
      (node (ref "U1") (pin "9") (pinfunction "PC1/ADC12_IN11_9") (pintype "bidirectional"))
    )
    (net (code "63") (name "unconnected-(U1B-PC4{slash}ADC12_IN14-Pad24)") (class "Default")
      (node (ref "U1") (pin "24") (pinfunction "PC4/ADC12_IN14_24") (pintype "bidirectional"))
    )
    (net (code "64") (name "unconnected-(U1B-PC5{slash}ADC12_IN15-Pad25)") (class "Default")
      (node (ref "U1") (pin "25") (pinfunction "PC5/ADC12_IN15_25") (pintype "bidirectional"))
    )
    (net (code "65") (name "unconnected-(U1B-PC6{slash}TIM3_CH1-Pad37)") (class "Default")
      (node (ref "U1") (pin "37") (pinfunction "PC6/TIM3_CH1_37") (pintype "bidirectional"))
    )
    (net (code "66") (name "unconnected-(U1B-PC7{slash}TIM3_CH2-Pad38)") (class "Default")
      (node (ref "U1") (pin "38") (pinfunction "PC7/TIM3_CH2_38") (pintype "bidirectional"))
    )
    (net (code "67") (name "unconnected-(U1B-PC8{slash}TIM3_CH3-Pad39)") (class "Default")
      (node (ref "U1") (pin "39") (pinfunction "PC8/TIM3_CH3_39") (pintype "bidirectional"))
    )
    (net (code "68") (name "unconnected-(U1B-PC9{slash}TIM3_CH4-Pad40)") (class "Default")
      (node (ref "U1") (pin "40") (pinfunction "PC9/TIM3_CH4_40") (pintype "bidirectional"))
    )
    (net (code "69") (name "unconnected-(U1B-PC10{slash}USART3_TX-Pad51)") (class "Default")
      (node (ref "U1") (pin "51") (pinfunction "PC10/USART3_TX_51") (pintype "bidirectional"))
    )
    (net (code "70") (name "unconnected-(U1B-PC11{slash}USART3_RX-Pad52)") (class "Default")
      (node (ref "U1") (pin "52") (pinfunction "PC11/USART3_RX_52") (pintype "bidirectional"))
    )
    (net (code "71") (name "unconnected-(U1B-PC12{slash}USART3_CK-Pad53)") (class "Default")
      (node (ref "U1") (pin "53") (pinfunction "PC12/USART3_CK_53") (pintype "bidirectional"))
    )
    (net (code "72") (name "unconnected-(U1B-PC13-TAMPER-RTC{slash}PC13{slash}TAMPER-RTC-Pad2)") (class "Default")
      (node (ref "U1") (pin "2") (pinfunction "PC13-TAMPER-RTC/PC13/TAMPER-RTC_2") (pintype "bidirectional"))
    )
    (net (code "73") (name "unconnected-(U1B-PC15-OSC32_OUT{slash}PC15{slash}OSC32_OUT-Pad4)") (class "Default")
      (node (ref "U1") (pin "4") (pinfunction "PC15-OSC32_OUT/PC15/OSC32_OUT_4") (pintype "bidirectional"))
    )
    (net (code "74") (name "unconnected-(U1B-PD2{slash}TIM3_ETR-Pad54)") (class "Default")
      (node (ref "U1") (pin "54") (pinfunction "PD2/TIM3_ETR_54") (pintype "bidirectional"))
    )
  )
)
